# Thetis_RevF6_SCH.net
KiCad netlist of a schematic drawn in EAGLE
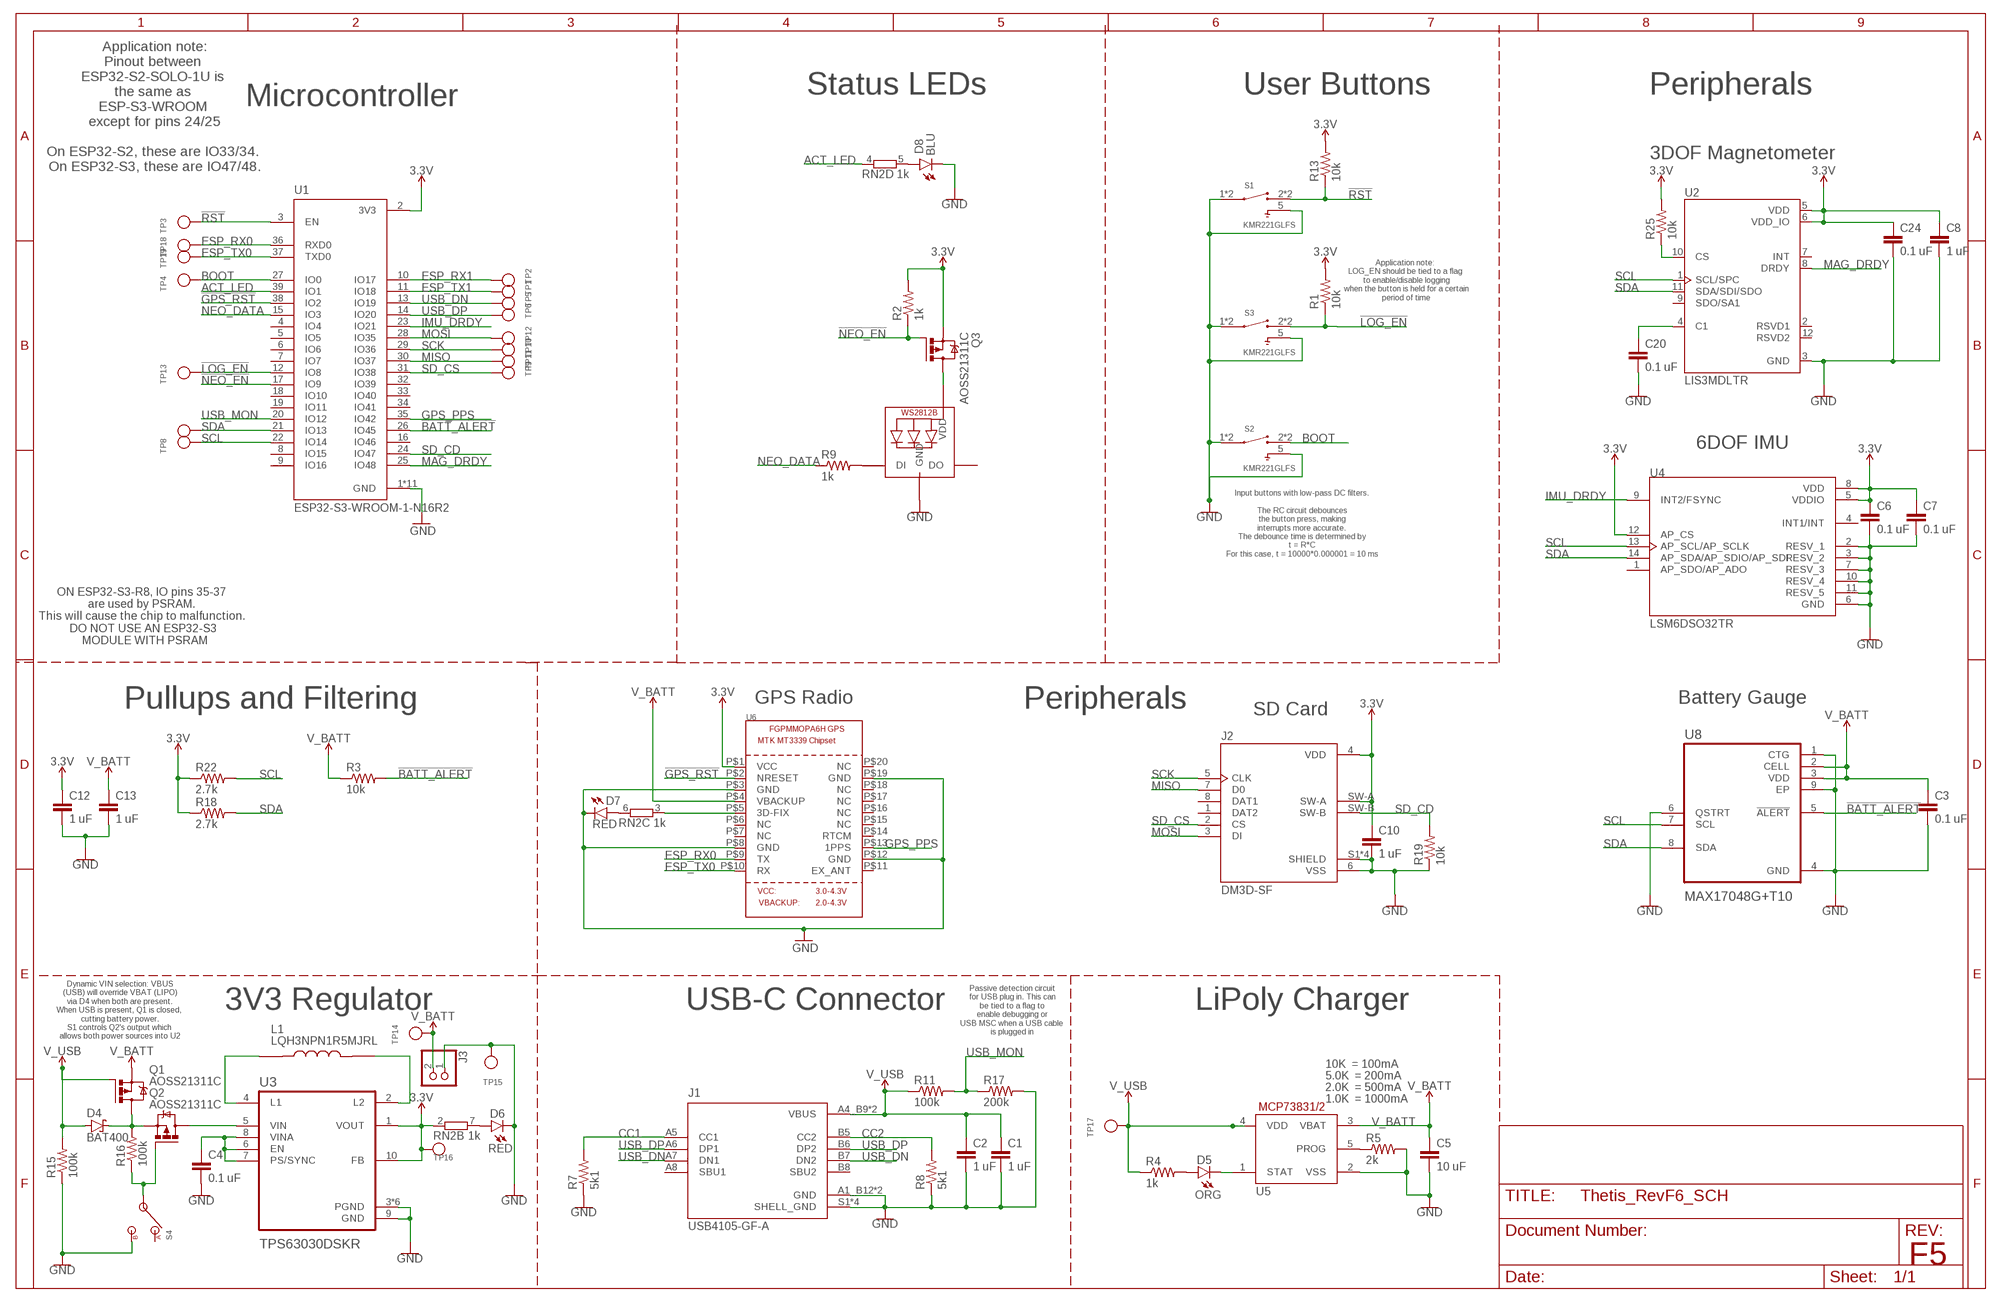
[diagram p0: schematic, sheet 1]

(export (version "E")
  (design (tool "Eeschema 10.0.6"))
  (components
    (comp (ref "C1")
      (value "1 uF")
      (footprint "eagle-import:C0603")
      (libsource (lib "eagle-import") (part "C-EUC0603"))
    )
    (comp (ref "C2")
      (value "1 uF")
      (footprint "eagle-import:C0603")
      (libsource (lib "eagle-import") (part "C-EUC0603"))
    )
    (comp (ref "C3")
      (value "0.1 uF")
      (footprint "eagle-import:C0603")
      (libsource (lib "eagle-import") (part "C-EUC0603"))
    )
    (comp (ref "C4")
      (value "0.1 uF")
      (footprint "eagle-import:C0603")
      (libsource (lib "eagle-import") (part "C-EUC0603"))
    )
    (comp (ref "C5")
      (value "10 uF")
      (footprint "eagle-import:C0603")
      (libsource (lib "eagle-import") (part "C-EUC0603"))
    )
    (comp (ref "C6")
      (value "0.1 uF")
      (footprint "eagle-import:C0603")
      (libsource (lib "eagle-import") (part "C-EUC0603"))
    )
    (comp (ref "C7")
      (value "0.1 uF")
      (footprint "eagle-import:C0603")
      (libsource (lib "eagle-import") (part "C-EUC0603"))
    )
    (comp (ref "C8")
      (value "1 uF")
      (footprint "eagle-import:C0603")
      (libsource (lib "eagle-import") (part "C-EUC0603"))
    )
    (comp (ref "C10")
      (value "1 uF")
      (footprint "eagle-import:C0603")
      (libsource (lib "eagle-import") (part "C-EUC0603"))
    )
    (comp (ref "C12")
      (value "1 uF")
      (footprint "eagle-import:C0603")
      (libsource (lib "eagle-import") (part "C-EUC0603"))
    )
    (comp (ref "C13")
      (value "1 uF")
      (footprint "eagle-import:C0603")
      (libsource (lib "eagle-import") (part "C-EUC0603"))
    )
    (comp (ref "C20")
      (value "0.1 uF")
      (footprint "eagle-import:C0603")
      (libsource (lib "eagle-import") (part "C-EUC0603"))
    )
    (comp (ref "C24")
      (value "0.1 uF")
      (footprint "eagle-import:C0603")
      (libsource (lib "eagle-import") (part "C-EUC0603"))
    )
    (comp (ref "D4")
      (value "BAT400")
      (footprint "eagle-import:SOT23")
      (libsource (lib "eagle-import") (part "BAS40"))
    )
    (comp (ref "D5")
      (value "ORG")
      (footprint "eagle-import:LEDC1608X65N")
      (libsource (lib "eagle-import") (part "CHIP-ROUND-G_0603"))
    )
    (comp (ref "D6")
      (value "RED")
      (footprint "eagle-import:LEDC1608X65N")
      (libsource (lib "eagle-import") (part "CHIP-ROUND-G_0603"))
    )
    (comp (ref "D7")
      (value "RED")
      (footprint "eagle-import:LEDC1608X35N")
      (libsource (lib "eagle-import") (part "CHIP-FLAT-Y_0603-0.35MM"))
    )
    (comp (ref "D8")
      (value "BLU")
      (footprint "eagle-import:LEDC1608X65N")
      (libsource (lib "eagle-import") (part "CHIP-ROUND-G_0603"))
    )
    (comp (ref "J1")
      (value "USB4105-GF-A")
      (footprint "eagle-import:GCT_USB4105-GF-A")
      (fields (field (name "MF") "GCT"))
      (libsource (lib "eagle-import") (part "USB4105-GF-A"))
    )
    (comp (ref "J2")
      (value "DM3D-SF")
      (footprint "eagle-import:HRS_DM3D-SF")
      (fields (field (name "MANUFACTURER") "Hirose"))
      (libsource (lib "eagle-import") (part "DM3D-SF"))
    )
    (comp (ref "J3")
      (value "JST_2PIN")
      (footprint "eagle-import:JSTPH2")
      (libsource (lib "eagle-import") (part "JST_2PIN"))
    )
    (comp (ref "L1")
      (value "LQH3NPN1R5MJRL")
      (footprint "eagle-import:IND_LQH3NPN1R5MJRL")
      (fields (field (name "DIGIKEY_PART_NUMBER") "490-9576-2-ND") (field (name "MF") "Murata Electronics"))
      (libsource (lib "eagle-import") (part "LQH3NPN1R5MJRL"))
    )
    (comp (ref "LED1")
      (value "WS2812B3535")
      (footprint "eagle-import:LED3535")
      (libsource (lib "eagle-import") (part "WS2812B3535"))
    )
    (comp (ref "Q1")
      (value "AOSS21311C")
      (footprint "eagle-import:SOT23")
      (fields (field (name "MANUFACTURER") "ON Semiconductor") (field (name "MPN") "BSS84"))
      (libsource (lib "eagle-import") (part "PMOSFET_BSS84"))
    )
    (comp (ref "Q2")
      (value "AOSS21311C")
      (footprint "eagle-import:SOT23")
      (fields (field (name "MANUFACTURER") "ON Semiconductor") (field (name "MPN") "BSS84"))
      (libsource (lib "eagle-import") (part "PMOSFET_BSS84"))
    )
    (comp (ref "Q3")
      (value "AOSS21311C")
      (footprint "eagle-import:SOT23")
      (fields (field (name "MANUFACTURER") "ON Semiconductor") (field (name "MPN") "BSS84"))
      (libsource (lib "eagle-import") (part "PMOSFET_BSS84"))
    )
    (comp (ref "R1")
      (value "10k")
      (footprint "eagle-import:R0603")
      (libsource (lib "eagle-import") (part "R-US_R0603"))
    )
    (comp (ref "R2")
      (value "1k")
      (footprint "eagle-import:R0603")
      (libsource (lib "eagle-import") (part "R-US_R0603"))
    )
    (comp (ref "R3")
      (value "10k")
      (footprint "eagle-import:R0603")
      (libsource (lib "eagle-import") (part "R-US_R0603"))
    )
    (comp (ref "R4")
      (value "1k")
      (footprint "eagle-import:R0603")
      (libsource (lib "eagle-import") (part "R-US_R0603"))
    )
    (comp (ref "R5")
      (value "2k")
      (footprint "eagle-import:R0603")
      (libsource (lib "eagle-import") (part "R-US_R0603"))
    )
    (comp (ref "R7")
      (value "5k1")
      (footprint "eagle-import:R0603")
      (libsource (lib "eagle-import") (part "R-US_R0603"))
    )
    (comp (ref "R8")
      (value "5k1")
      (footprint "eagle-import:R0603")
      (libsource (lib "eagle-import") (part "R-US_R0603"))
    )
    (comp (ref "R9")
      (value "1k")
      (footprint "eagle-import:R0603")
      (libsource (lib "eagle-import") (part "R-US_R0603"))
    )
    (comp (ref "R11")
      (value "100k")
      (footprint "eagle-import:R0603")
      (libsource (lib "eagle-import") (part "R-US_R0603"))
    )
    (comp (ref "R13")
      (value "10k")
      (footprint "eagle-import:R0603")
      (libsource (lib "eagle-import") (part "R-US_R0603"))
    )
    (comp (ref "R15")
      (value "100k")
      (footprint "eagle-import:R0603")
      (libsource (lib "eagle-import") (part "R-US_R0603"))
    )
    (comp (ref "R16")
      (value "100k")
      (footprint "eagle-import:R0603")
      (libsource (lib "eagle-import") (part "R-US_R0603"))
    )
    (comp (ref "R17")
      (value "200k")
      (footprint "eagle-import:R0603")
      (libsource (lib "eagle-import") (part "R-US_R0603"))
    )
    (comp (ref "R18")
      (value "2.7k")
      (footprint "eagle-import:R0603")
      (libsource (lib "eagle-import") (part "R-US_R0603"))
    )
    (comp (ref "R19")
      (value "10k")
      (footprint "eagle-import:R0603")
      (libsource (lib "eagle-import") (part "R-US_R0603"))
    )
    (comp (ref "R22")
      (value "2.7k")
      (footprint "eagle-import:R0603")
      (libsource (lib "eagle-import") (part "R-US_R0603"))
    )
    (comp (ref "R25")
      (value "10k")
      (footprint "eagle-import:R0603")
      (libsource (lib "eagle-import") (part "R-US_R0603"))
    )
    (comp (ref "RN2")
      (value "1k")
      (footprint "eagle-import:EXBN8V")
      (libsource (lib "eagle-import") (part "4R-NEXBN8V"))
    )
    (comp (ref "S1")
      (value "KMR221GLFS")
      (footprint "eagle-import:SW_KMR221GLFS")
      (fields (field (name "MANUFACTURER") "CnK"))
      (libsource (lib "eagle-import") (part "KMR221GLFS"))
    )
    (comp (ref "S2")
      (value "KMR221GLFS")
      (footprint "eagle-import:SW_KMR221GLFS")
      (fields (field (name "MANUFACTURER") "CnK"))
      (libsource (lib "eagle-import") (part "KMR221GLFS"))
    )
    (comp (ref "S3")
      (value "KMR221GLFS")
      (footprint "eagle-import:SW_KMR221GLFS")
      (fields (field (name "MANUFACTURER") "CnK"))
      (libsource (lib "eagle-import") (part "KMR221GLFS"))
    )
    (comp (ref "S4")
      (value "CL-SB-12X")
      (footprint "eagle-import:CL-SB-12A")
      (libsource (lib "eagle-import") (part "CL-SB-12X"))
    )
    (comp (ref "TP1")
      (value "TESTPOINT1.5X2.0MM_NOCREAM")
      (footprint "eagle-import:PAD-1.5X2.0")
      (libsource (lib "eagle-import") (part "TESTPOINT1.5X2.0MM_NOCREAM"))
    )
    (comp (ref "TP2")
      (value "TESTPOINT1.5X2.0MM_NOCREAM")
      (footprint "eagle-import:PAD-1.5X2.0")
      (libsource (lib "eagle-import") (part "TESTPOINT1.5X2.0MM_NOCREAM"))
    )
    (comp (ref "TP3")
      (value "TESTPOINT1.5X2.0MM_NOCREAM")
      (footprint "eagle-import:PAD-1.5X2.0")
      (libsource (lib "eagle-import") (part "TESTPOINT1.5X2.0MM_NOCREAM"))
    )
    (comp (ref "TP4")
      (value "TESTPOINT1.5X2.0MM_NOCREAM")
      (footprint "eagle-import:PAD-1.5X2.0")
      (libsource (lib "eagle-import") (part "TESTPOINT1.5X2.0MM_NOCREAM"))
    )
    (comp (ref "TP5")
      (value "TESTPOINT1.5X2.0MM_NOCREAM")
      (footprint "eagle-import:PAD-1.5X2.0")
      (libsource (lib "eagle-import") (part "TESTPOINT1.5X2.0MM_NOCREAM"))
    )
    (comp (ref "TP6")
      (value "TESTPOINT1.5X2.0MM_NOCREAM")
      (footprint "eagle-import:PAD-1.5X2.0")
      (libsource (lib "eagle-import") (part "TESTPOINT1.5X2.0MM_NOCREAM"))
    )
    (comp (ref "TP7")
      (value "TESTPOINT1.5X2.0MM_NOCREAM")
      (footprint "eagle-import:PAD-1.5X2.0")
      (libsource (lib "eagle-import") (part "TESTPOINT1.5X2.0MM_NOCREAM"))
    )
    (comp (ref "TP8")
      (value "TESTPOINT1.5X2.0MM_NOCREAM")
      (footprint "eagle-import:PAD-1.5X2.0")
      (libsource (lib "eagle-import") (part "TESTPOINT1.5X2.0MM_NOCREAM"))
    )
    (comp (ref "TP9")
      (value "TESTPOINT1.5X2.0MM_NOCREAM")
      (footprint "eagle-import:PAD-1.5X2.0")
      (libsource (lib "eagle-import") (part "TESTPOINT1.5X2.0MM_NOCREAM"))
    )
    (comp (ref "TP10")
      (value "TESTPOINT1.5X2.0MM_NOCREAM")
      (footprint "eagle-import:PAD-1.5X2.0")
      (libsource (lib "eagle-import") (part "TESTPOINT1.5X2.0MM_NOCREAM"))
    )
    (comp (ref "TP11")
      (value "TESTPOINT1.5X2.0MM_NOCREAM")
      (footprint "eagle-import:PAD-1.5X2.0")
      (libsource (lib "eagle-import") (part "TESTPOINT1.5X2.0MM_NOCREAM"))
    )
    (comp (ref "TP12")
      (value "TESTPOINT1.5X2.0MM_NOCREAM")
      (footprint "eagle-import:PAD-1.5X2.0")
      (libsource (lib "eagle-import") (part "TESTPOINT1.5X2.0MM_NOCREAM"))
    )
    (comp (ref "TP13")
      (value "TESTPOINT1.5X2.0MM_NOCREAM")
      (footprint "eagle-import:PAD-1.5X2.0")
      (libsource (lib "eagle-import") (part "TESTPOINT1.5X2.0MM_NOCREAM"))
    )
    (comp (ref "TP14")
      (value "TESTPOINT1.5X2.0MM_NOCREAM")
      (footprint "eagle-import:PAD-1.5X2.0")
      (libsource (lib "eagle-import") (part "TESTPOINT1.5X2.0MM_NOCREAM"))
    )
    (comp (ref "TP15")
      (value "TESTPOINT1.5X2.0MM_NOCREAM")
      (footprint "eagle-import:PAD-1.5X2.0")
      (libsource (lib "eagle-import") (part "TESTPOINT1.5X2.0MM_NOCREAM"))
    )
    (comp (ref "TP16")
      (value "TESTPOINT1.5X2.0MM_NOCREAM")
      (footprint "eagle-import:PAD-1.5X2.0")
      (libsource (lib "eagle-import") (part "TESTPOINT1.5X2.0MM_NOCREAM"))
    )
    (comp (ref "TP17")
      (value "TESTPOINT1.5X2.0MM_NOCREAM")
      (footprint "eagle-import:PAD-1.5X2.0")
      (libsource (lib "eagle-import") (part "TESTPOINT1.5X2.0MM_NOCREAM"))
    )
    (comp (ref "TP18")
      (value "TESTPOINT1.5X2.0MM_NOCREAM")
      (footprint "eagle-import:PAD-1.5X2.0")
      (libsource (lib "eagle-import") (part "TESTPOINT1.5X2.0MM_NOCREAM"))
    )
    (comp (ref "TP19")
      (value "TESTPOINT1.5X2.0MM_NOCREAM")
      (footprint "eagle-import:PAD-1.5X2.0")
      (libsource (lib "eagle-import") (part "TESTPOINT1.5X2.0MM_NOCREAM"))
    )
    (comp (ref "U1")
      (value "ESP32-S3-WROOM-1-N16R2")
      (footprint "eagle-import:XCVR_ESP32-S3-WROOM-1-N16R2")
      (fields (field (name "MF") "Espressif Systems"))
      (libsource (lib "eagle-import") (part "ESP32-S3-WROOM-1-N16R2"))
    )
    (comp (ref "U2")
      (value "LIS3MDLTR")
      (footprint "eagle-import:XDCR_LIS3MDLTR")
      (fields (field (name "MF") "STMicroelectronics"))
      (libsource (lib "eagle-import") (part "LIS3MDLTR"))
    )
    (comp (ref "U3")
      (value "TPS63030DSKR")
      (footprint "eagle-import:SON50P250X250X80-11N")
      (fields (field (name "MF") "Texas Instruments"))
      (libsource (lib "eagle-import") (part "TPS63030DSKR"))
    )
    (comp (ref "U4")
      (value "LSM6DSO32TR")
      (footprint "eagle-import:PQFN50P300X250X97-14N")
      (fields (field (name "MANUFACTURER") "TDK Corporation"))
      (libsource (lib "eagle-import") (part "LSM6DSO32TR"))
    )
    (comp (ref "U5")
      (value "MCP73831/OT")
      (footprint "eagle-import:SOT23-5L")
      (libsource (lib "eagle-import") (part "MCP73831/OT"))
    )
    (comp (ref "U6")
      (value "GPS_FGPMMOPA6H")
      (footprint "eagle-import:FGPMMOPA6H")
      (libsource (lib "eagle-import") (part "GPS_FGPMMOPA6H"))
    )
    (comp (ref "U8")
      (value "MAX17048G+T10")
      (footprint "eagle-import:SON50P200X200X80-9N")
      (libsource (lib "eagle-import") (part "MAX17048G+T10"))
    )
  )
  (nets
    (net (code "1") (name "/ACT_LED") (class "Default")
      (node (ref "RN2") (pin "4") (pinfunction "1_4") (pintype "passive"))
      (node (ref "U1") (pin "39") (pinfunction "IO1_39") (pintype "bidirectional"))
    )
    (net (code "2") (name "/BOOT") (class "Default")
      (node (ref "S2") (pin "2") (pinfunction "3_2") (pintype "passive"))
      (node (ref "S2") (pin "3") (pinfunction "3_3") (pintype "passive"))
      (node (ref "TP4") (pin "P$1") (pinfunction "P$1_P$1") (pintype "bidirectional"))
      (node (ref "U1") (pin "27") (pinfunction "IO0_27") (pintype "bidirectional"))
    )
    (net (code "3") (name "/CC1") (class "Default")
      (node (ref "J1") (pin "A5") (pinfunction "CC1_A5") (pintype "bidirectional"))
      (node (ref "R7") (pin "2") (pinfunction "2_2") (pintype "passive"))
    )
    (net (code "4") (name "/CC2") (class "Default")
      (node (ref "J1") (pin "B5") (pinfunction "CC2_B5") (pintype "bidirectional"))
      (node (ref "R8") (pin "2") (pinfunction "2_2") (pintype "passive"))
    )
    (net (code "5") (name "/ESP_RX0") (class "Default")
      (node (ref "TP18") (pin "P$1") (pinfunction "P$1_P$1") (pintype "bidirectional"))
      (node (ref "U1") (pin "36") (pinfunction "RXD0_36") (pintype "bidirectional"))
      (node (ref "U6") (pin "P$9") (pinfunction "TX_P$9") (pintype "bidirectional"))
    )
    (net (code "6") (name "/ESP_RX1") (class "Default")
      (node (ref "TP2") (pin "P$1") (pinfunction "P$1_P$1") (pintype "bidirectional"))
      (node (ref "U1") (pin "10") (pinfunction "IO17_10") (pintype "bidirectional"))
    )
    (net (code "7") (name "/ESP_TX0") (class "Default")
      (node (ref "TP19") (pin "P$1") (pinfunction "P$1_P$1") (pintype "bidirectional"))
      (node (ref "U1") (pin "37") (pinfunction "TXD0_37") (pintype "bidirectional"))
      (node (ref "U6") (pin "P$10") (pinfunction "RX_P$10") (pintype "bidirectional"))
    )
    (net (code "8") (name "/ESP_TX1") (class "Default")
      (node (ref "TP1") (pin "P$1") (pinfunction "P$1_P$1") (pintype "bidirectional"))
      (node (ref "U1") (pin "11") (pinfunction "IO18_11") (pintype "bidirectional"))
    )
    (net (code "9") (name "/GPS_PPS") (class "Default")
      (node (ref "U1") (pin "35") (pinfunction "IO42_35") (pintype "bidirectional"))
      (node (ref "U6") (pin "P$13") (pinfunction "1PPS_P$13") (pintype "bidirectional"))
    )
    (net (code "10") (name "/IMU_DRDY") (class "Default")
      (node (ref "U1") (pin "23") (pinfunction "IO21_23") (pintype "bidirectional"))
      (node (ref "U4") (pin "9") (pinfunction "INT2/FSYNC_9") (pintype "bidirectional"))
    )
    (net (code "11") (name "/MAG_DRDY") (class "Default")
      (node (ref "U1") (pin "25") (pinfunction "IO48_25") (pintype "bidirectional"))
      (node (ref "U2") (pin "8") (pinfunction "DRDY_8") (pintype "output"))
    )
    (net (code "12") (name "/MISO") (class "Default")
      (node (ref "J2") (pin "7") (pinfunction "D0_7") (pintype "bidirectional"))
      (node (ref "TP11") (pin "P$1") (pinfunction "P$1_P$1") (pintype "bidirectional"))
      (node (ref "U1") (pin "30") (pinfunction "IO37_30") (pintype "bidirectional"))
    )
    (net (code "13") (name "/MOSI") (class "Default")
      (node (ref "J2") (pin "3") (pinfunction "DI_3") (pintype "bidirectional"))
      (node (ref "TP12") (pin "P$1") (pinfunction "P$1_P$1") (pintype "bidirectional"))
      (node (ref "U1") (pin "28") (pinfunction "IO35_28") (pintype "bidirectional"))
    )
    (net (code "14") (name "/NEO_DATA") (class "Default")
      (node (ref "R9") (pin "1") (pinfunction "1_1") (pintype "passive"))
      (node (ref "U1") (pin "15") (pinfunction "IO3_15") (pintype "bidirectional"))
    )
    (net (code "15") (name "/SCK") (class "Default")
      (node (ref "J2") (pin "5") (pinfunction "CLK_5") (pintype "bidirectional"))
      (node (ref "TP10") (pin "P$1") (pinfunction "P$1_P$1") (pintype "bidirectional"))
      (node (ref "U1") (pin "29") (pinfunction "IO36_29") (pintype "bidirectional"))
    )
    (net (code "16") (name "/SCL") (class "Default")
      (node (ref "R22") (pin "2") (pinfunction "2_2") (pintype "passive"))
      (node (ref "TP8") (pin "P$1") (pinfunction "P$1_P$1") (pintype "bidirectional"))
      (node (ref "U1") (pin "22") (pinfunction "IO14_22") (pintype "bidirectional"))
      (node (ref "U2") (pin "1") (pinfunction "SCL/SPC_1") (pintype "input"))
      (node (ref "U4") (pin "13") (pinfunction "AP_SCL/AP_SCLK_13") (pintype "input"))
      (node (ref "U8") (pin "7") (pinfunction "SCL_7") (pintype "input"))
    )
    (net (code "17") (name "/SDA") (class "Default")
      (node (ref "R18") (pin "2") (pinfunction "2_2") (pintype "passive"))
      (node (ref "TP7") (pin "P$1") (pinfunction "P$1_P$1") (pintype "bidirectional"))
      (node (ref "U1") (pin "21") (pinfunction "IO13_21") (pintype "bidirectional"))
      (node (ref "U2") (pin "11") (pinfunction "SDA/SDI/SDO_11") (pintype "bidirectional"))
      (node (ref "U4") (pin "14") (pinfunction "AP_SDA/AP_SDIO/AP_SDI_14") (pintype "bidirectional"))
      (node (ref "U8") (pin "8") (pinfunction "SDA_8") (pintype "bidirectional"))
    )
    (net (code "18") (name "/SD_CD") (class "Default")
      (node (ref "J2") (pin "SW-B") (pinfunction "SW-B_SW-B") (pintype "bidirectional"))
      (node (ref "R19") (pin "2") (pinfunction "2_2") (pintype "passive"))
      (node (ref "U1") (pin "24") (pinfunction "IO47_24") (pintype "bidirectional"))
    )
    (net (code "19") (name "/SD_CS") (class "Default")
      (node (ref "J2") (pin "2") (pinfunction "CS_2") (pintype "bidirectional"))
      (node (ref "TP9") (pin "P$1") (pinfunction "P$1_P$1") (pintype "bidirectional"))
      (node (ref "U1") (pin "31") (pinfunction "IO38_31") (pintype "bidirectional"))
    )
    (net (code "20") (name "/USB_DN") (class "Default")
      (node (ref "J1") (pin "A7") (pinfunction "DN1_A7") (pintype "bidirectional"))
      (node (ref "J1") (pin "B7") (pinfunction "DN2_B7") (pintype "bidirectional"))
      (node (ref "TP5") (pin "P$1") (pinfunction "P$1_P$1") (pintype "bidirectional"))
      (node (ref "U1") (pin "13") (pinfunction "IO19_13") (pintype "bidirectional"))
    )
    (net (code "21") (name "/USB_DP") (class "Default")
      (node (ref "J1") (pin "A6") (pinfunction "DP1_A6") (pintype "bidirectional"))
      (node (ref "J1") (pin "B6") (pinfunction "DP2_B6") (pintype "bidirectional"))
      (node (ref "TP6") (pin "P$1") (pinfunction "P$1_P$1") (pintype "bidirectional"))
      (node (ref "U1") (pin "14") (pinfunction "IO20_14") (pintype "bidirectional"))
    )
    (net (code "22") (name "/USB_MON") (class "Default")
      (node (ref "R11") (pin "2") (pinfunction "2_2") (pintype "passive"))
      (node (ref "R17") (pin "1") (pinfunction "1_1") (pintype "passive"))
      (node (ref "U1") (pin "20") (pinfunction "IO12_20") (pintype "bidirectional"))
    )
    (net (code "23") (name "/~{BATT_ALERT}") (class "Default")
      (node (ref "R3") (pin "2") (pinfunction "2_2") (pintype "passive"))
      (node (ref "U1") (pin "26") (pinfunction "IO45_26") (pintype "bidirectional"))
      (node (ref "U8") (pin "5") (pinfunction "~{ALERT}_5") (pintype "output"))
    )
    (net (code "24") (name "/~{GPS_RST}") (class "Default")
      (node (ref "U1") (pin "38") (pinfunction "IO2_38") (pintype "bidirectional"))
      (node (ref "U6") (pin "P$2") (pinfunction "NRESET_P$2") (pintype "bidirectional"))
    )
    (net (code "25") (name "/~{LOG_EN}") (class "Default")
      (node (ref "R1") (pin "1") (pinfunction "1_1") (pintype "passive"))
      (node (ref "S3") (pin "2") (pinfunction "3_2") (pintype "passive"))
      (node (ref "S3") (pin "3") (pinfunction "3_3") (pintype "passive"))
      (node (ref "TP13") (pin "P$1") (pinfunction "P$1_P$1") (pintype "bidirectional"))
      (node (ref "U1") (pin "12") (pinfunction "IO8_12") (pintype "bidirectional"))
    )
    (net (code "26") (name "/~{NEO_EN}") (class "Default")
      (node (ref "Q3") (pin "1") (pinfunction "G_1") (pintype "passive"))
      (node (ref "R2") (pin "1") (pinfunction "1_1") (pintype "passive"))
      (node (ref "U1") (pin "17") (pinfunction "IO9_17") (pintype "bidirectional"))
    )
    (net (code "27") (name "/~{RST}") (class "Default")
      (node (ref "R13") (pin "1") (pinfunction "1_1") (pintype "passive"))
      (node (ref "S1") (pin "2") (pinfunction "3_2") (pintype "passive"))
      (node (ref "S1") (pin "3") (pinfunction "3_3") (pintype "passive"))
      (node (ref "TP3") (pin "P$1") (pinfunction "P$1_P$1") (pintype "bidirectional"))
      (node (ref "U1") (pin "3") (pinfunction "EN_3") (pintype "input"))
    )
    (net (code "28") (name "3.3V") (class "Default")
      (node (ref "C10") (pin "1") (pinfunction "1_1") (pintype "passive"))
      (node (ref "C12") (pin "1") (pinfunction "1_1") (pintype "passive"))
      (node (ref "C24") (pin "1") (pinfunction "1_1") (pintype "passive"))
      (node (ref "C6") (pin "1") (pinfunction "1_1") (pintype "passive"))
      (node (ref "C7") (pin "1") (pinfunction "1_1") (pintype "passive"))
      (node (ref "C8") (pin "1") (pinfunction "1_1") (pintype "passive"))
      (node (ref "J2") (pin "4") (pinfunction "VDD_4") (pintype "power_in"))
      (node (ref "J2") (pin "SW-A") (pinfunction "SW-A_SW-A") (pintype "bidirectional"))
      (node (ref "Q3") (pin "2") (pinfunction "S_2") (pintype "passive"))
      (node (ref "R1") (pin "2") (pinfunction "2_2") (pintype "passive"))
      (node (ref "R13") (pin "2") (pinfunction "2_2") (pintype "passive"))
      (node (ref "R18") (pin "1") (pinfunction "1_1") (pintype "passive"))
      (node (ref "R2") (pin "2") (pinfunction "2_2") (pintype "passive"))
      (node (ref "R22") (pin "1") (pinfunction "1_1") (pintype "passive"))
      (node (ref "R25") (pin "2") (pinfunction "2_2") (pintype "passive"))
      (node (ref "RN2") (pin "2") (pinfunction "1_2") (pintype "passive"))
      (node (ref "TP16") (pin "P$1") (pinfunction "P$1_P$1") (pintype "bidirectional"))
      (node (ref "U1") (pin "2") (pinfunction "3V3_2") (pintype "power_in"))
      (node (ref "U2") (pin "5") (pinfunction "VDD_5") (pintype "power_in"))
      (node (ref "U2") (pin "6") (pinfunction "VDD_IO_6") (pintype "power_in"))
      (node (ref "U3") (pin "1") (pinfunction "VOUT_1") (pintype "output"))
      (node (ref "U3") (pin "10") (pinfunction "FB_10") (pintype "input"))
      (node (ref "U4") (pin "12") (pinfunction "AP_CS_12") (pintype "input"))
      (node (ref "U4") (pin "5") (pinfunction "VDDIO_5") (pintype "power_in"))
      (node (ref "U4") (pin "8") (pinfunction "VDD_8") (pintype "power_in"))
      (node (ref "U6") (pin "P$1") (pinfunction "VCC_P$1") (pintype "bidirectional"))
    )
    (net (code "29") (name "GND") (class "Default")
      (node (ref "C1") (pin "2") (pinfunction "2_2") (pintype "passive"))
      (node (ref "C10") (pin "2") (pinfunction "2_2") (pintype "passive"))
      (node (ref "C12") (pin "2") (pinfunction "2_2") (pintype "passive"))
      (node (ref "C13") (pin "2") (pinfunction "2_2") (pintype "passive"))
      (node (ref "C2") (pin "2") (pinfunction "2_2") (pintype "passive"))
      (node (ref "C20") (pin "2") (pinfunction "2_2") (pintype "passive"))
      (node (ref "C24") (pin "2") (pinfunction "2_2") (pintype "passive"))
      (node (ref "C3") (pin "2") (pinfunction "2_2") (pintype "passive"))
      (node (ref "C4") (pin "2") (pinfunction "2_2") (pintype "passive"))
      (node (ref "C5") (pin "2") (pinfunction "2_2") (pintype "passive"))
      (node (ref "C6") (pin "2") (pinfunction "2_2") (pintype "passive"))
      (node (ref "C7") (pin "2") (pinfunction "2_2") (pintype "passive"))
      (node (ref "C8") (pin "2") (pinfunction "2_2") (pintype "passive"))
      (node (ref "D6") (pin "C") (pinfunction "C_C") (pintype "passive"))
      (node (ref "D7") (pin "C") (pinfunction "C_C") (pintype "passive"))
      (node (ref "D8") (pin "C") (pinfunction "C_C") (pintype "passive"))
      (node (ref "J1") (pin "A1_B12") (pinfunction "GND_A1_B12") (pintype "power_in"))
      (node (ref "J1") (pin "B1_A12") (pinfunction "GND_B1_A12") (pintype "power_in"))
      (node (ref "J1") (pin "S1") (pinfunction "SHELL_GND_S1") (pintype "power_in"))
      (node (ref "J1") (pin "S2") (pinfunction "SHELL_GND_S2") (pintype "power_in"))
      (node (ref "J1") (pin "S3") (pinfunction "SHELL_GND_S3") (pintype "power_in"))
      (node (ref "J1") (pin "S4") (pinfunction "SHELL_GND_S4") (pintype "power_in"))
      (node (ref "J2") (pin "6") (pinfunction "VSS_6") (pintype "power_in"))
      (node (ref "J2") (pin "S1") (pinfunction "SHIELD_S1") (pintype "passive"))
      (node (ref "J2") (pin "S2") (pinfunction "SHIELD_S2") (pintype "passive"))
      (node (ref "J2") (pin "S3") (pinfunction "SHIELD_S3") (pintype "passive"))
      (node (ref "J2") (pin "S4") (pinfunction "SHIELD_S4") (pintype "passive"))
      (node (ref "J3") (pin "1") (pinfunction "1_1") (pintype "passive"))
      (node (ref "LED1") (pin "4") (pinfunction "GND_4") (pintype "power_in"))
      (node (ref "R15") (pin "1") (pinfunction "1_1") (pintype "passive"))
      (node (ref "R17") (pin "2") (pinfunction "2_2") (pintype "passive"))
      (node (ref "R19") (pin "1") (pinfunction "1_1") (pintype "passive"))
      (node (ref "R5") (pin "2") (pinfunction "2_2") (pintype "passive"))
      (node (ref "R7") (pin "1") (pinfunction "1_1") (pintype "passive"))
      (node (ref "R8") (pin "1") (pinfunction "1_1") (pintype "passive"))
      (node (ref "S1") (pin "1") (pinfunction "1_1") (pintype "passive"))
      (node (ref "S1") (pin "4") (pinfunction "1_4") (pintype "passive"))
      (node (ref "S1") (pin "5") (pinfunction "5_5") (pintype "passive"))
      (node (ref "S2") (pin "1") (pinfunction "1_1") (pintype "passive"))
      (node (ref "S2") (pin "4") (pinfunction "1_4") (pintype "passive"))
      (node (ref "S2") (pin "5") (pinfunction "5_5") (pintype "passive"))
      (node (ref "S3") (pin "1") (pinfunction "1_1") (pintype "passive"))
      (node (ref "S3") (pin "4") (pinfunction "1_4") (pintype "passive"))
      (node (ref "S3") (pin "5") (pinfunction "5_5") (pintype "passive"))
      (node (ref "S4") (pin "3") (pinfunction "3_3") (pintype "bidirectional"))
      (node (ref "TP15") (pin "P$1") (pinfunction "P$1_P$1") (pintype "bidirectional"))
      (node (ref "U1") (pin "1") (pinfunction "GND_1") (pintype "power_in"))
      (node (ref "U1") (pin "40") (pinfunction "GND_40") (pintype "power_in"))
      (node (ref "U1") (pin "41_1") (pinfunction "GND_41_1") (pintype "power_in"))
      (node (ref "U1") (pin "41_2") (pinfunction "GND_41_2") (pintype "power_in"))
      (node (ref "U1") (pin "41_3") (pinfunction "GND_41_3") (pintype "power_in"))
      (node (ref "U1") (pin "41_4") (pinfunction "GND_41_4") (pintype "power_in"))
      (node (ref "U1") (pin "41_5") (pinfunction "GND_41_5") (pintype "power_in"))
      (node (ref "U1") (pin "41_6") (pinfunction "GND_41_6") (pintype "power_in"))
      (node (ref "U1") (pin "41_7") (pinfunction "GND_41_7") (pintype "power_in"))
      (node (ref "U1") (pin "41_8") (pinfunction "GND_41_8") (pintype "power_in"))
      (node (ref "U1") (pin "41_9") (pinfunction "GND_41_9") (pintype "power_in"))
      (node (ref "U2") (pin "3") (pinfunction "GND_3") (pintype "power_in"))
      (node (ref "U3") (pin "11") (pinfunction "PGND_11") (pintype "power_in"))
      (node (ref "U3") (pin "12") (pinfunction "PGND_12") (pintype "power_in"))
      (node (ref "U3") (pin "13") (pinfunction "PGND_13") (pintype "power_in"))
      (node (ref "U3") (pin "14") (pinfunction "PGND_14") (pintype "power_in"))
      (node (ref "U3") (pin "15") (pinfunction "PGND_15") (pintype "power_in"))
      (node (ref "U3") (pin "3") (pinfunction "PGND_3") (pintype "power_in"))
      (node (ref "U3") (pin "9") (pinfunction "GND_9") (pintype "power_in"))
      (node (ref "U4") (pin "10") (pinfunction "RESV_4_10") (pintype "bidirectional"))
      (node (ref "U4") (pin "11") (pinfunction "RESV_5_11") (pintype "bidirectional"))
      (node (ref "U4") (pin "2") (pinfunction "RESV_1_2") (pintype "bidirectional"))
      (node (ref "U4") (pin "3") (pinfunction "RESV_2_3") (pintype "bidirectional"))
      (node (ref "U4") (pin "6") (pinfunction "GND_6") (pintype "power_in"))
      (node (ref "U4") (pin "7") (pinfunction "RESV_3_7") (pintype "bidirectional"))
      (node (ref "U5") (pin "2") (pinfunction "VSS_2") (pintype "power_in"))
      (node (ref "U6") (pin "P$12") (pinfunction "GND_P$12") (pintype "bidirectional"))
      (node (ref "U6") (pin "P$19") (pinfunction "GND_P$19") (pintype "bidirectional"))
      (node (ref "U6") (pin "P$3") (pinfunction "GND_P$3") (pintype "bidirectional"))
      (node (ref "U6") (pin "P$8") (pinfunction "GND_P$8") (pintype "bidirectional"))
      (node (ref "U8") (pin "1") (pinfunction "CTG_1") (pintype "power_in"))
      (node (ref "U8") (pin "4") (pinfunction "GND_4") (pintype "power_in"))
      (node (ref "U8") (pin "6") (pinfunction "QSTRT_6") (pintype "input"))
      (node (ref "U8") (pin "9") (pinfunction "EP_9") (pintype "power_in"))
    )
    (net (code "30") (name "Net-(D4-C)") (class "Default")
      (node (ref "D4") (pin "3") (pinfunction "C_3") (pintype "passive"))
      (node (ref "Q1") (pin "3") (pinfunction "D_3") (pintype "passive"))
      (node (ref "Q2") (pin "2") (pinfunction "S_2") (pintype "passive"))
      (node (ref "R16") (pin "2") (pinfunction "2_2") (pintype "passive"))
    )
    (net (code "31") (name "Net-(D5-PadA)") (class "Default")
      (node (ref "D5") (pin "A") (pinfunction "A_A") (pintype "passive"))
      (node (ref "R4") (pin "2") (pinfunction "2_2") (pintype "passive"))
    )
    (net (code "32") (name "Net-(LED1-DI)") (class "Default")
      (node (ref "LED1") (pin "1") (pinfunction "DI_1") (pintype "input"))
      (node (ref "R9") (pin "2") (pinfunction "2_2") (pintype "passive"))
    )
    (net (code "33") (name "Net-(LED1-VDD)") (class "Default")
      (node (ref "LED1") (pin "2") (pinfunction "VDD_2") (pintype "power_in"))
      (node (ref "Q3") (pin "3") (pinfunction "D_3") (pintype "passive"))
    )
    (net (code "34") (name "Net-(Q2-D)") (class "Default")
      (node (ref "Q2") (pin "3") (pinfunction "D_3") (pintype "passive"))
      (node (ref "U3") (pin "5") (pinfunction "VIN_5") (pintype "input"))
    )
    (net (code "35") (name "Net-(Q2-G)") (class "Default")
      (node (ref "Q2") (pin "1") (pinfunction "G_1") (pintype "passive"))
      (node (ref "R16") (pin "1") (pinfunction "1_1") (pintype "passive"))
      (node (ref "S4") (pin "2") (pinfunction "2_2") (pintype "bidirectional"))
    )
    (net (code "36") (name "Net-(RN2B-2)") (class "Default")
      (node (ref "D6") (pin "A") (pinfunction "A_A") (pintype "passive"))
      (node (ref "RN2") (pin "7") (pinfunction "2_7") (pintype "passive"))
    )
    (net (code "37") (name "Net-(RN2C-1)") (class "Default")
      (node (ref "RN2") (pin "3") (pinfunction "1_3") (pintype "passive"))
      (node (ref "U6") (pin "P$5") (pinfunction "3D-FIX_P$5") (pintype "bidirectional"))
    )
    (net (code "38") (name "Net-(RN2C-2)") (class "Default")
      (node (ref "D7") (pin "A") (pinfunction "A_A") (pintype "passive"))
      (node (ref "RN2") (pin "6") (pinfunction "2_6") (pintype "passive"))
    )
    (net (code "39") (name "Net-(RN2D-2)") (class "Default")
      (node (ref "D8") (pin "A") (pinfunction "A_A") (pintype "passive"))
      (node (ref "RN2") (pin "5") (pinfunction "2_5") (pintype "passive"))
    )
    (net (code "40") (name "Net-(U2-C1)") (class "Default")
      (node (ref "C20") (pin "1") (pinfunction "1_1") (pintype "passive"))
      (node (ref "U2") (pin "4") (pinfunction "C1_4") (pintype "passive"))
    )
    (net (code "41") (name "Net-(U2-CS)") (class "Default")
      (node (ref "R25") (pin "1") (pinfunction "1_1") (pintype "passive"))
      (node (ref "U2") (pin "10") (pinfunction "CS_10") (pintype "input"))
    )
    (net (code "42") (name "Net-(U3-EN)") (class "Default")
      (node (ref "C4") (pin "1") (pinfunction "1_1") (pintype "passive"))
      (node (ref "U3") (pin "6") (pinfunction "EN_6") (pintype "input"))
      (node (ref "U3") (pin "7") (pinfunction "PS/SYNC_7") (pintype "input"))
      (node (ref "U3") (pin "8") (pinfunction "VINA_8") (pintype "input"))
    )
    (net (code "43") (name "Net-(U3-L1)") (class "Default")
      (node (ref "L1") (pin "1") (pinfunction "1_1") (pintype "passive"))
      (node (ref "U3") (pin "4") (pinfunction "L1_4") (pintype "input"))
    )
    (net (code "44") (name "Net-(U3-L2)") (class "Default")
      (node (ref "L1") (pin "2") (pinfunction "2_2") (pintype "passive"))
      (node (ref "U3") (pin "2") (pinfunction "L2_2") (pintype "input"))
    )
    (net (code "45") (name "Net-(U5-PROG)") (class "Default")
      (node (ref "R5") (pin "1") (pinfunction "1_1") (pintype "passive"))
      (node (ref "U5") (pin "5") (pinfunction "PROG_5") (pintype "input"))
    )
    (net (code "46") (name "Net-(U5-STAT)") (class "Default")
      (node (ref "D5") (pin "C") (pinfunction "C_C") (pintype "passive"))
      (node (ref "U5") (pin "1") (pinfunction "STAT_1") (pintype "output"))
    )
    (net (code "47") (name "V_BATT") (class "Default")
      (node (ref "C13") (pin "1") (pinfunction "1_1") (pintype "passive"))
      (node (ref "C3") (pin "1") (pinfunction "1_1") (pintype "passive"))
      (node (ref "C5") (pin "1") (pinfunction "1_1") (pintype "passive"))
      (node (ref "J3") (pin "2") (pinfunction "2_2") (pintype "passive"))
      (node (ref "Q1") (pin "2") (pinfunction "S_2") (pintype "passive"))
      (node (ref "R3") (pin "1") (pinfunction "1_1") (pintype "passive"))
      (node (ref "TP14") (pin "P$1") (pinfunction "P$1_P$1") (pintype "bidirectional"))
      (node (ref "U5") (pin "3") (pinfunction "VBAT_3") (pintype "bidirectional"))
      (node (ref "U6") (pin "P$4") (pinfunction "VBACKUP_P$4") (pintype "bidirectional"))
      (node (ref "U8") (pin "2") (pinfunction "CELL_2") (pintype "power_in"))
      (node (ref "U8") (pin "3") (pinfunction "VDD_3") (pintype "power_in"))
    )
    (net (code "48") (name "V_USB") (class "Default")
      (node (ref "C1") (pin "1") (pinfunction "1_1") (pintype "passive"))
      (node (ref "C2") (pin "1") (pinfunction "1_1") (pintype "passive"))
      (node (ref "D4") (pin "1") (pinfunction "A_1") (pintype "passive"))
      (node (ref "J1") (pin "A4_B9") (pinfunction "VBUS_A4_B9") (pintype "power_in"))
      (node (ref "J1") (pin "B4_A9") (pinfunction "VBUS_B4_A9") (pintype "power_in"))
      (node (ref "Q1") (pin "1") (pinfunction "G_1") (pintype "passive"))
      (node (ref "R11") (pin "1") (pinfunction "1_1") (pintype "passive"))
      (node (ref "R15") (pin "2") (pinfunction "2_2") (pintype "passive"))
      (node (ref "R4") (pin "1") (pinfunction "1_1") (pintype "passive"))
      (node (ref "TP17") (pin "P$1") (pinfunction "P$1_P$1") (pintype "bidirectional"))
      (node (ref "U5") (pin "4") (pinfunction "VDD_4") (pintype "power_in"))
    )
    (net (code "49") (name "unconnected-(J1-SBU1-PadA8)") (class "Default")
      (node (ref "J1") (pin "A8") (pinfunction "SBU1_A8") (pintype "bidirectional"))
    )
    (net (code "50") (name "unconnected-(J1-SBU2-PadB8)") (class "Default")
      (node (ref "J1") (pin "B8") (pinfunction "SBU2_B8") (pintype "bidirectional"))
    )
    (net (code "51") (name "unconnected-(J2-DAT1-Pad8)") (class "Default")
      (node (ref "J2") (pin "8") (pinfunction "DAT1_8") (pintype "bidirectional"))
    )
    (net (code "52") (name "unconnected-(J2-DAT2-Pad1)") (class "Default")
      (node (ref "J2") (pin "1") (pinfunction "DAT2_1") (pintype "bidirectional"))
    )
    (net (code "53") (name "unconnected-(LED1-DO-Pad3)") (class "Default")
      (node (ref "LED1") (pin "3") (pinfunction "DO_3") (pintype "output"))
    )
    (net (code "54") (name "unconnected-(S4-Pad1)") (class "Default")
      (node (ref "S4") (pin "1") (pinfunction "1_1") (pintype "bidirectional"))
    )
    (net (code "55") (name "unconnected-(U1-IO4-Pad4)") (class "Default")
      (node (ref "U1") (pin "4") (pinfunction "IO4_4") (pintype "bidirectional"))
    )
    (net (code "56") (name "unconnected-(U1-IO5-Pad5)") (class "Default")
      (node (ref "U1") (pin "5") (pinfunction "IO5_5") (pintype "bidirectional"))
    )
    (net (code "57") (name "unconnected-(U1-IO6-Pad6)") (class "Default")
      (node (ref "U1") (pin "6") (pinfunction "IO6_6") (pintype "bidirectional"))
    )
    (net (code "58") (name "unconnected-(U1-IO7-Pad7)") (class "Default")
      (node (ref "U1") (pin "7") (pinfunction "IO7_7") (pintype "bidirectional"))
    )
    (net (code "59") (name "unconnected-(U1-IO10-Pad18)") (class "Default")
      (node (ref "U1") (pin "18") (pinfunction "IO10_18") (pintype "bidirectional"))
    )
    (net (code "60") (name "unconnected-(U1-IO11-Pad19)") (class "Default")
      (node (ref "U1") (pin "19") (pinfunction "IO11_19") (pintype "bidirectional"))
    )
    (net (code "61") (name "unconnected-(U1-IO15-Pad8)") (class "Default")
      (node (ref "U1") (pin "8") (pinfunction "IO15_8") (pintype "bidirectional"))
    )
    (net (code "62") (name "unconnected-(U1-IO16-Pad9)") (class "Default")
      (node (ref "U1") (pin "9") (pinfunction "IO16_9") (pintype "bidirectional"))
    )
    (net (code "63") (name "unconnected-(U1-IO39-Pad32)") (class "Default")
      (node (ref "U1") (pin "32") (pinfunction "IO39_32") (pintype "bidirectional"))
    )
    (net (code "64") (name "unconnected-(U1-IO40-Pad33)") (class "Default")
      (node (ref "U1") (pin "33") (pinfunction "IO40_33") (pintype "bidirectional"))
    )
    (net (code "65") (name "unconnected-(U1-IO41-Pad34)") (class "Default")
      (node (ref "U1") (pin "34") (pinfunction "IO41_34") (pintype "bidirectional"))
    )
    (net (code "66") (name "unconnected-(U1-IO46-Pad16)") (class "Default")
      (node (ref "U1") (pin "16") (pinfunction "IO46_16") (pintype "bidirectional"))
    )
    (net (code "67") (name "unconnected-(U2-INT-Pad7)") (class "Default")
      (node (ref "U2") (pin "7") (pinfunction "INT_7") (pintype "output"))
    )
    (net (code "68") (name "unconnected-(U2-RSVD1-Pad2)") (class "Default")
      (node (ref "U2") (pin "2") (pinfunction "RSVD1_2") (pintype "passive"))
    )
    (net (code "69") (name "unconnected-(U2-RSVD2-Pad12)") (class "Default")
      (node (ref "U2") (pin "12") (pinfunction "RSVD2_12") (pintype "passive"))
    )
    (net (code "70") (name "unconnected-(U2-SDO{slash}SA1-Pad9)") (class "Default")
      (node (ref "U2") (pin "9") (pinfunction "SDO/SA1_9") (pintype "bidirectional"))
    )
    (net (code "71") (name "unconnected-(U4-AP_SDO{slash}AP_ADO-Pad1)") (class "Default")
      (node (ref "U4") (pin "1") (pinfunction "AP_SDO/AP_ADO_1") (pintype "output"))
    )
    (net (code "72") (name "unconnected-(U4-INT1{slash}INT-Pad4)") (class "Default")
      (node (ref "U4") (pin "4") (pinfunction "INT1/INT_4") (pintype "output"))
    )
    (net (code "73") (name "unconnected-(U6-EX_ANT-PadP$11)") (class "Default")
      (node (ref "U6") (pin "P$11") (pinfunction "EX_ANT_P$11") (pintype "bidirectional"))
    )
    (net (code "74") (name "unconnected-(U6-NC-PadP$6)") (class "Default")
      (node (ref "U6") (pin "P$6") (pinfunction "NC_P$6") (pintype "bidirectional"))
    )
    (net (code "75") (name "unconnected-(U6-NC-PadP$7)") (class "Default")
      (node (ref "U6") (pin "P$7") (pinfunction "NC_P$7") (pintype "bidirectional"))
    )
    (net (code "76") (name "unconnected-(U6-NC-PadP$15)") (class "Default")
      (node (ref "U6") (pin "P$15") (pinfunction "NC_P$15") (pintype "bidirectional"))
    )
    (net (code "77") (name "unconnected-(U6-NC-PadP$16)") (class "Default")
      (node (ref "U6") (pin "P$16") (pinfunction "NC_P$16") (pintype "bidirectional"))
    )
    (net (code "78") (name "unconnected-(U6-NC-PadP$17)") (class "Default")
      (node (ref "U6") (pin "P$17") (pinfunction "NC_P$17") (pintype "bidirectional"))
    )
    (net (code "79") (name "unconnected-(U6-NC-PadP$18)") (class "Default")
      (node (ref "U6") (pin "P$18") (pinfunction "NC_P$18") (pintype "bidirectional"))
    )
    (net (code "80") (name "unconnected-(U6-NC-PadP$20)") (class "Default")
      (node (ref "U6") (pin "P$20") (pinfunction "NC_P$20") (pintype "bidirectional"))
    )
    (net (code "81") (name "unconnected-(U6-RTCM-PadP$14)") (class "Default")
      (node (ref "U6") (pin "P$14") (pinfunction "RTCM_P$14") (pintype "bidirectional"))
    )
  )
)
